# kbd2snes.net
KiCad netlist of a schematic drawn in EAGLE
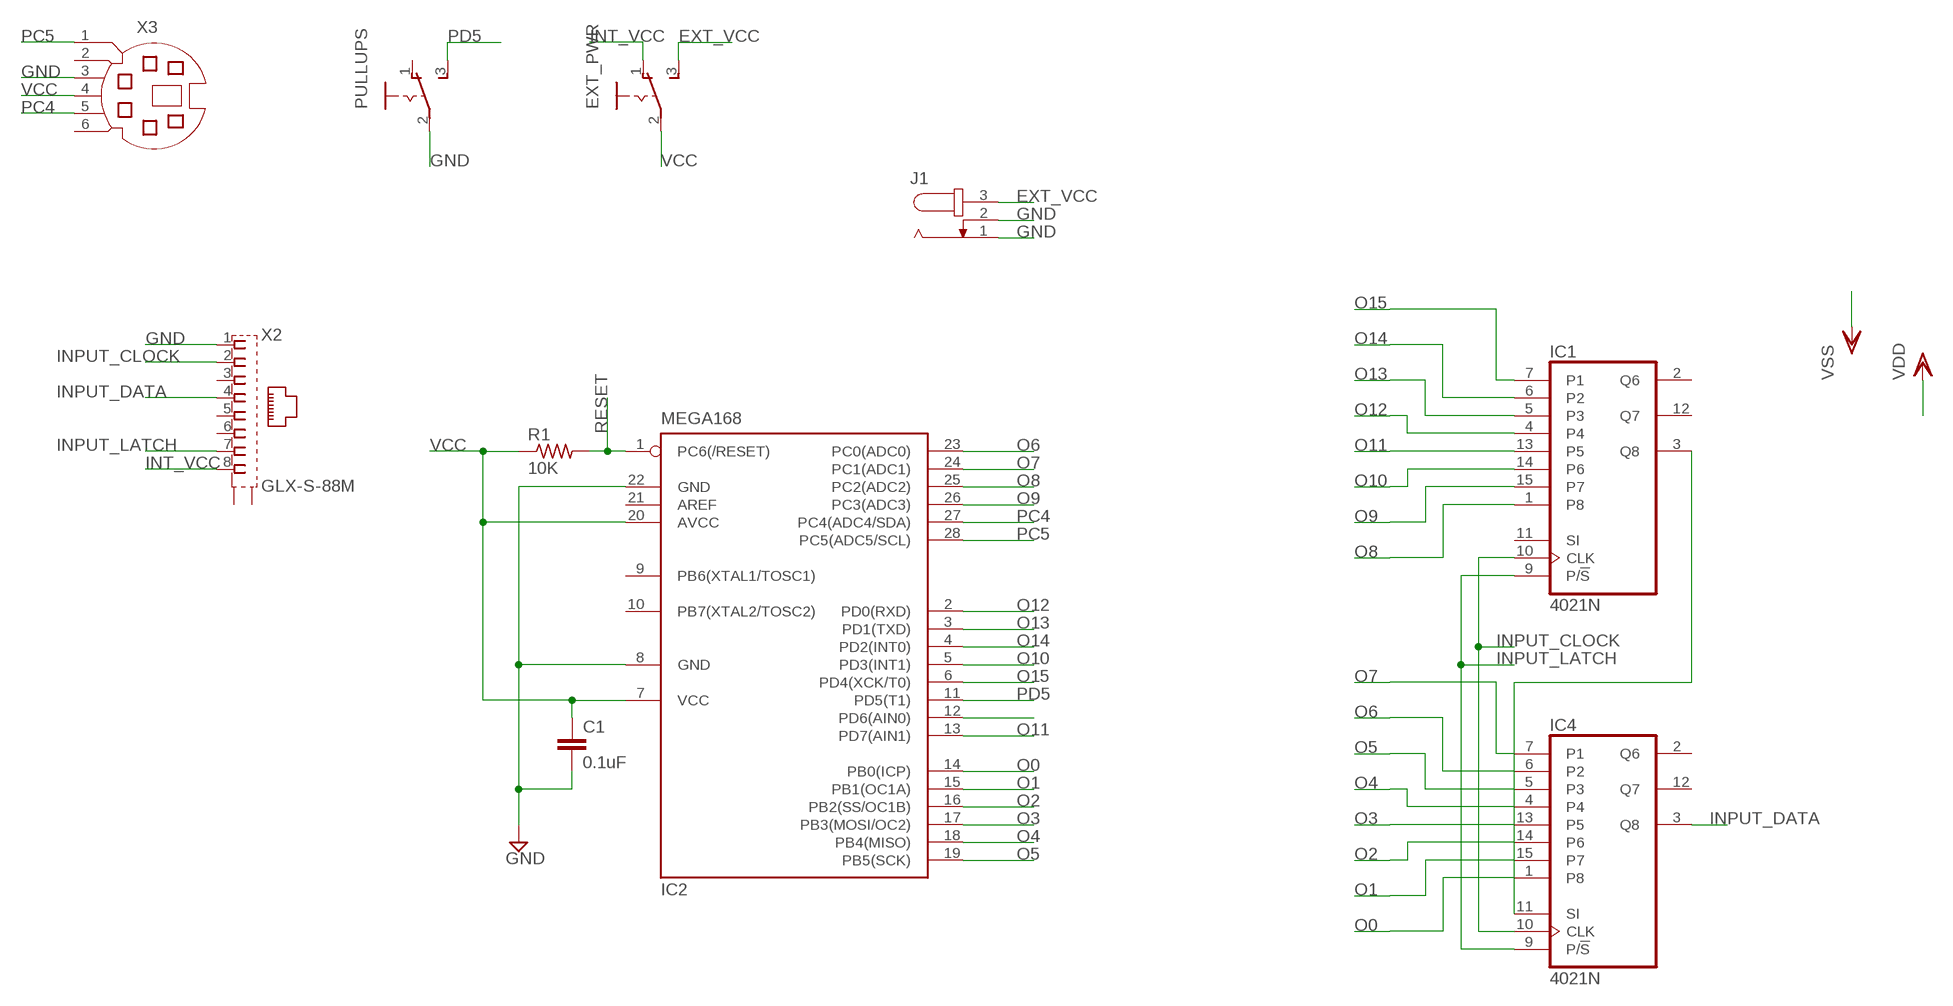
[diagram p0: schematic, sheet 1]

(export (version "E")
  (design (tool "Eeschema 10.0.6"))
  (components
    (comp (ref "C1")
      (value "0.1uF")
      (footprint "eagle-import:C050-024X044")
      (libsource (lib "eagle-import") (part "C-EU050-024X044"))
    )
    (comp (ref "EXT_PWR")
      (value "CHAVE")
      (footprint "eagle-import:CHAVE")
      (libsource (lib "eagle-import") (part "CHAVE"))
    )
    (comp (ref "IC1")
      (value "4021N")
      (footprint "eagle-import:DIL16")
      (libsource (lib "eagle-import") (part "4021N"))
    )
    (comp (ref "IC2")
      (value "MEGA168")
      (footprint "eagle-import:DIL28-3")
      (libsource (lib "eagle-import") (part "MEGA8-P"))
    )
    (comp (ref "IC4")
      (value "4021N")
      (footprint "eagle-import:DIL16")
      (libsource (lib "eagle-import") (part "4021N"))
    )
    (comp (ref "J1")
      (value "JACK-PLUG1")
      (footprint "eagle-import:SPC4078")
      (libsource (lib "eagle-import") (part "JACK-PLUG1"))
    )
    (comp (ref "PULLUPS")
      (value "CHAVE")
      (footprint "eagle-import:CHAVE")
      (libsource (lib "eagle-import") (part "CHAVE"))
    )
    (comp (ref "R1")
      (value "10K")
      (footprint "eagle-import:0207_7")
      (libsource (lib "eagle-import") (part "R-US_0207/7"))
    )
    (comp (ref "X2")
      (value "GLX-S-88M")
      (footprint "eagle-import:GLX-S-88M")
      (libsource (lib "eagle-import") (part "GLX-S-88M"))
    )
    (comp (ref "X3")
      (value "MD06SS")
      (footprint "eagle-import:MDIN06SS")
      (libsource (lib "eagle-import") (part "MD06SS"))
    )
  )
  (nets
    (net (code "1") (name "/EXT_VCC") (class "Default")
      (node (ref "EXT_PWR") (pin "3") (pinfunction "S_3") (pintype "passive"))
      (node (ref "J1") (pin "3") (pinfunction "3_3") (pintype "passive"))
    )
    (net (code "2") (name "/INPUT_CLOCK") (class "Default")
      (node (ref "IC1") (pin "10") (pinfunction "CLK_10") (pintype "input"))
      (node (ref "IC4") (pin "10") (pinfunction "CLK_10") (pintype "input"))
      (node (ref "X2") (pin "2") (pinfunction "2_2") (pintype "passive"))
    )
    (net (code "3") (name "/INPUT_DATA") (class "Default")
      (node (ref "IC4") (pin "3") (pinfunction "Q8_3") (pintype "output"))
      (node (ref "X2") (pin "4") (pinfunction "4_4") (pintype "passive"))
    )
    (net (code "4") (name "/INPUT_LATCH") (class "Default")
      (node (ref "IC1") (pin "9") (pinfunction "P/~{S}_9") (pintype "input"))
      (node (ref "IC4") (pin "9") (pinfunction "P/~{S}_9") (pintype "input"))
      (node (ref "X2") (pin "7") (pinfunction "7_7") (pintype "passive"))
    )
    (net (code "5") (name "/INT_VCC") (class "Default")
      (node (ref "EXT_PWR") (pin "1") (pinfunction "O_1") (pintype "passive"))
      (node (ref "X2") (pin "8") (pinfunction "8_8") (pintype "passive"))
    )
    (net (code "6") (name "/O0") (class "Default")
      (node (ref "IC2") (pin "14") (pinfunction "PB0(ICP)_14") (pintype "bidirectional"))
      (node (ref "IC4") (pin "1") (pinfunction "P8_1") (pintype "input"))
    )
    (net (code "7") (name "/O1") (class "Default")
      (node (ref "IC2") (pin "15") (pinfunction "PB1(OC1A)_15") (pintype "bidirectional"))
      (node (ref "IC4") (pin "15") (pinfunction "P7_15") (pintype "input"))
    )
    (net (code "8") (name "/O2") (class "Default")
      (node (ref "IC2") (pin "16") (pinfunction "PB2(SS/OC1B)_16") (pintype "bidirectional"))
      (node (ref "IC4") (pin "14") (pinfunction "P6_14") (pintype "input"))
    )
    (net (code "9") (name "/O3") (class "Default")
      (node (ref "IC2") (pin "17") (pinfunction "PB3(MOSI/OC2)_17") (pintype "bidirectional"))
      (node (ref "IC4") (pin "13") (pinfunction "P5_13") (pintype "input"))
    )
    (net (code "10") (name "/O4") (class "Default")
      (node (ref "IC2") (pin "18") (pinfunction "PB4(MISO)_18") (pintype "bidirectional"))
      (node (ref "IC4") (pin "4") (pinfunction "P4_4") (pintype "input"))
    )
    (net (code "11") (name "/O5") (class "Default")
      (node (ref "IC2") (pin "19") (pinfunction "PB5(SCK)_19") (pintype "bidirectional"))
      (node (ref "IC4") (pin "5") (pinfunction "P3_5") (pintype "input"))
    )
    (net (code "12") (name "/O6") (class "Default")
      (node (ref "IC2") (pin "23") (pinfunction "PC0(ADC0)_23") (pintype "bidirectional"))
      (node (ref "IC4") (pin "6") (pinfunction "P2_6") (pintype "input"))
    )
    (net (code "13") (name "/O7") (class "Default")
      (node (ref "IC2") (pin "24") (pinfunction "PC1(ADC1)_24") (pintype "bidirectional"))
      (node (ref "IC4") (pin "7") (pinfunction "P1_7") (pintype "input"))
    )
    (net (code "14") (name "/O8") (class "Default")
      (node (ref "IC1") (pin "1") (pinfunction "P8_1") (pintype "input"))
      (node (ref "IC2") (pin "25") (pinfunction "PC2(ADC2)_25") (pintype "bidirectional"))
    )
    (net (code "15") (name "/O9") (class "Default")
      (node (ref "IC1") (pin "15") (pinfunction "P7_15") (pintype "input"))
      (node (ref "IC2") (pin "26") (pinfunction "PC3(ADC3)_26") (pintype "bidirectional"))
    )
    (net (code "16") (name "/O10") (class "Default")
      (node (ref "IC1") (pin "14") (pinfunction "P6_14") (pintype "input"))
      (node (ref "IC2") (pin "5") (pinfunction "PD3(INT1)_5") (pintype "bidirectional"))
    )
    (net (code "17") (name "/O11") (class "Default")
      (node (ref "IC1") (pin "13") (pinfunction "P5_13") (pintype "input"))
      (node (ref "IC2") (pin "13") (pinfunction "PD7(AIN1)_13") (pintype "bidirectional"))
    )
    (net (code "18") (name "/O12") (class "Default")
      (node (ref "IC1") (pin "4") (pinfunction "P4_4") (pintype "input"))
      (node (ref "IC2") (pin "2") (pinfunction "PD0(RXD)_2") (pintype "bidirectional"))
    )
    (net (code "19") (name "/O13") (class "Default")
      (node (ref "IC1") (pin "5") (pinfunction "P3_5") (pintype "input"))
      (node (ref "IC2") (pin "3") (pinfunction "PD1(TXD)_3") (pintype "bidirectional"))
    )
    (net (code "20") (name "/O14") (class "Default")
      (node (ref "IC1") (pin "6") (pinfunction "P2_6") (pintype "input"))
      (node (ref "IC2") (pin "4") (pinfunction "PD2(INT0)_4") (pintype "bidirectional"))
    )
    (net (code "21") (name "/O15") (class "Default")
      (node (ref "IC1") (pin "7") (pinfunction "P1_7") (pintype "input"))
      (node (ref "IC2") (pin "6") (pinfunction "PD4(XCK/T0)_6") (pintype "bidirectional"))
    )
    (net (code "22") (name "/PC4") (class "Default")
      (node (ref "IC2") (pin "27") (pinfunction "PC4(ADC4/SDA)_27") (pintype "bidirectional"))
      (node (ref "X3") (pin "5") (pinfunction "5_5") (pintype "passive"))
    )
    (net (code "23") (name "/PC5") (class "Default")
      (node (ref "IC2") (pin "28") (pinfunction "PC5(ADC5/SCL)_28") (pintype "bidirectional"))
      (node (ref "X3") (pin "1") (pinfunction "1_1") (pintype "passive"))
    )
    (net (code "24") (name "/PD5") (class "Default")
      (node (ref "IC2") (pin "11") (pinfunction "PD5(T1)_11") (pintype "bidirectional"))
      (node (ref "PULLUPS") (pin "3") (pinfunction "S_3") (pintype "passive"))
    )
    (net (code "25") (name "/RESET") (class "Default")
      (node (ref "IC2") (pin "1") (pinfunction "PC6(/RESET)_1") (pintype "bidirectional"))
      (node (ref "R1") (pin "2") (pinfunction "2_2") (pintype "passive"))
    )
    (net (code "26") (name "/VCC") (class "Default")
      (node (ref "C1") (pin "1") (pinfunction "1_1") (pintype "passive"))
      (node (ref "EXT_PWR") (pin "2") (pinfunction "P_2") (pintype "passive"))
      (node (ref "IC2") (pin "20") (pinfunction "AVCC_20") (pintype "power_in"))
      (node (ref "IC2") (pin "7") (pinfunction "VCC_7") (pintype "power_in"))
      (node (ref "R1") (pin "1") (pinfunction "1_1") (pintype "passive"))
      (node (ref "X3") (pin "4") (pinfunction "4_4") (pintype "passive"))
    )
    (net (code "27") (name "GND") (class "Default")
      (node (ref "C1") (pin "2") (pinfunction "2_2") (pintype "passive"))
      (node (ref "IC2") (pin "22") (pinfunction "GND_22") (pintype "power_in"))
      (node (ref "IC2") (pin "8") (pinfunction "GND_8") (pintype "power_in"))
      (node (ref "J1") (pin "1") (pinfunction "1_1") (pintype "passive"))
      (node (ref "J1") (pin "2") (pinfunction "2_2") (pintype "passive"))
      (node (ref "PULLUPS") (pin "2") (pinfunction "P_2") (pintype "passive"))
      (node (ref "X2") (pin "1") (pinfunction "1_1") (pintype "passive"))
      (node (ref "X3") (pin "3") (pinfunction "3_3") (pintype "passive"))
    )
    (net (code "28") (name "Net-(IC1A-Q8)") (class "Default")
      (node (ref "IC1") (pin "3") (pinfunction "Q8_3") (pintype "output"))
      (node (ref "IC4") (pin "11") (pinfunction "SI_11") (pintype "input"))
    )
    (net (code "31") (name "unconnected-(IC1A-Q6-Pad2)") (class "Default")
      (node (ref "IC1") (pin "2") (pinfunction "Q6_2") (pintype "output"))
    )
    (net (code "32") (name "unconnected-(IC1A-Q7-Pad12)") (class "Default")
      (node (ref "IC1") (pin "12") (pinfunction "Q7_12") (pintype "output"))
    )
    (net (code "33") (name "unconnected-(IC1A-SI-Pad11)") (class "Default")
      (node (ref "IC1") (pin "11") (pinfunction "SI_11") (pintype "input"))
    )
    (net (code "34") (name "unconnected-(IC2-AREF-Pad21)") (class "Default")
      (node (ref "IC2") (pin "21") (pinfunction "AREF_21") (pintype "passive"))
    )
    (net (code "35") (name "unconnected-(IC2-PB6(XTAL1{slash}TOSC1)-Pad9)") (class "Default")
      (node (ref "IC2") (pin "9") (pinfunction "PB6(XTAL1/TOSC1)_9") (pintype "bidirectional"))
    )
    (net (code "36") (name "unconnected-(IC2-PB7(XTAL2{slash}TOSC2)-Pad10)") (class "Default")
      (node (ref "IC2") (pin "10") (pinfunction "PB7(XTAL2/TOSC2)_10") (pintype "bidirectional"))
    )
    (net (code "37") (name "unconnected-(IC2-PD6(AIN0)-Pad12)") (class "Default")
      (node (ref "IC2") (pin "12") (pinfunction "PD6(AIN0)_12") (pintype "bidirectional"))
    )
    (net (code "38") (name "unconnected-(IC4A-Q6-Pad2)") (class "Default")
      (node (ref "IC4") (pin "2") (pinfunction "Q6_2") (pintype "output"))
    )
    (net (code "39") (name "unconnected-(IC4A-Q7-Pad12)") (class "Default")
      (node (ref "IC4") (pin "12") (pinfunction "Q7_12") (pintype "output"))
    )
    (net (code "40") (name "unconnected-(PULLUPS-O-Pad1)") (class "Default")
      (node (ref "PULLUPS") (pin "1") (pinfunction "O_1") (pintype "passive"))
    )
    (net (code "41") (name "unconnected-(X2-Pad3)") (class "Default")
      (node (ref "X2") (pin "3") (pinfunction "3_3") (pintype "passive"))
    )
    (net (code "42") (name "unconnected-(X2-Pad5)") (class "Default")
      (node (ref "X2") (pin "5") (pinfunction "5_5") (pintype "passive"))
    )
    (net (code "43") (name "unconnected-(X2-Pad6)") (class "Default")
      (node (ref "X2") (pin "6") (pinfunction "6_6") (pintype "passive"))
    )
    (net (code "44") (name "unconnected-(X2-PadS1)") (class "Default")
      (node (ref "X2") (pin "S1") (pinfunction "S1_S1") (pintype "passive"))
    )
    (net (code "45") (name "unconnected-(X2-PadS2)") (class "Default")
      (node (ref "X2") (pin "S2") (pinfunction "S2_S2") (pintype "passive"))
    )
    (net (code "46") (name "unconnected-(X3-Pad2)") (class "Default")
      (node (ref "X3") (pin "2") (pinfunction "2_2") (pintype "passive"))
    )
    (net (code "47") (name "unconnected-(X3-Pad6)") (class "Default")
      (node (ref "X3") (pin "6") (pinfunction "6_6") (pintype "passive"))
    )
  )
)
